# mcu1.net
KiCad netlist of a schematic drawn in Altium Designer
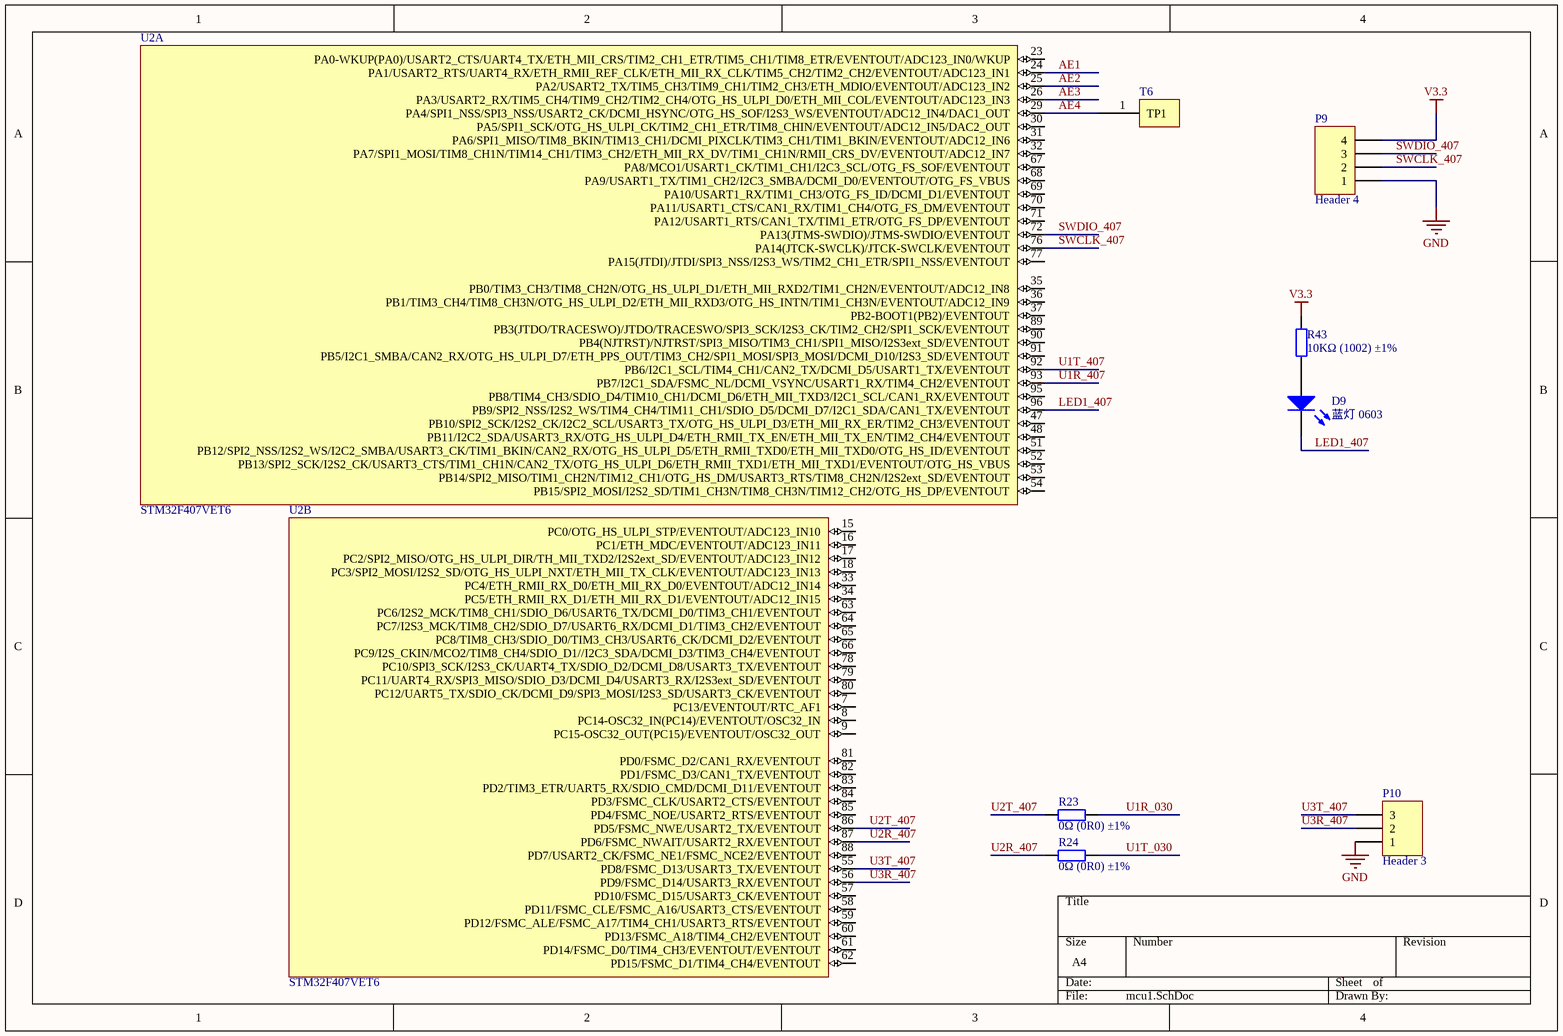
[diagram p0: mcu1.SchDoc]

(export (version "E")
  (design (tool "Eeschema 10.0.6"))
  (components
    (comp (ref "D9")
      (value "蓝灯 0603")
      (footprint "0603_LED_S1")
      (description "发光二极管")
      (libsource (lib "Miscellaneous Devices LC") (part "0603 蓝灯"))
    )
    (comp (ref "P9")
      (value "Header 4")
      (footprint "HDR1X4")
      (description "Header, 4-Pin")
      (fields (field (name "PUBLISHER") "Altium Limited"))
      (libsource (lib "Miscellaneous Connectors") (part "Header 4"))
    )
    (comp (ref "P10")
      (value "Header 3")
      (footprint "HDR1X3")
      (description "Header, 3-Pin")
      (fields (field (name "PUBLISHER") "Altium Limited"))
      (libsource (lib "Miscellaneous Connectors") (part "Header 3"))
    )
    (comp (ref "R23")
      (value "0Ω (0R0) ±1%")
      (footprint "0603_R")
      (description "贴片电阻")
      (libsource (lib "Miscellaneous Devices LC") (part "0603 0Ω (0R0) 1%"))
    )
    (comp (ref "R24")
      (value "0Ω (0R0) ±1%")
      (footprint "0603_R")
      (description "贴片电阻")
      (libsource (lib "Miscellaneous Devices LC") (part "0603 0Ω (0R0) 1%"))
    )
    (comp (ref "R43")
      (value "10KΩ (1002) ±1%")
      (footprint "0603_R")
      (description "贴片电阻")
      (libsource (lib "Miscellaneous Devices LC") (part "0603 10KΩ (1002) 1%"))
    )
    (comp (ref "T6") (value "TP1") (footprint "TP1") (libsource (lib "CHK-I") (part "TP1")))
    (comp (ref "U2")
      (value "STM32F407VET6")
      (footprint "LQFP-100_14x14x05P")
      (description "ARM")
      (libsource (lib "Miscellaneous Devices LC") (part "STM32F407VET6"))
    )
  )
  (nets
    (net (code "1") (name "/AE1") (class "Default")
      (node (ref "U2") (pin "24") (pinfunction "PA1/USART2_RTS/UART4_RX/ETH_RMII_REF_CLK/ETH_MII_RX_CLK/TIM5_CH2/TIM2_CH2/EVENTOUT/ADC123_IN1_24") (pintype "bidirectional"))
    )
    (net (code "2") (name "/AE2") (class "Default")
      (node (ref "U2") (pin "25") (pinfunction "PA2/USART2_TX/TIM5_CH3/TIM9_CH1/TIM2_CH3/ETH_MDIO/EVENTOUT/ADC123_IN2_25") (pintype "bidirectional"))
    )
    (net (code "3") (name "/AE3") (class "Default")
      (node (ref "U2") (pin "26") (pinfunction "PA3/USART2_RX/TIM5_CH4/TIM9_CH2/TIM2_CH4/OTG_HS_ULPI_D0/ETH_MII_COL/EVENTOUT/ADC123_IN3_26") (pintype "bidirectional"))
    )
    (net (code "4") (name "/AE4") (class "Default")
      (node (ref "T6") (pin "1") (pinfunction "TP1_1") (pintype "passive"))
      (node (ref "U2") (pin "29") (pinfunction "PA4/SPI1_NSS/SPI3_NSS/USART2_CK/DCMI_HSYNC/OTG_HS_SOF/I2S3_WS/EVENTOUT/ADC12_IN4/DAC1_OUT_29") (pintype "bidirectional"))
    )
    (net (code "5") (name "/LED1_407") (class "Default")
      (node (ref "D9") (pin "K") (pinfunction "K_K") (pintype "passive"))
      (node (ref "U2") (pin "96") (pinfunction "PB9/SPI2_NSS/I2S2_WS/TIM4_CH4/TIM11_CH1/SDIO_D5/DCMI_D7/I2C1_SDA/CAN1_TX/EVENTOUT_96") (pintype "bidirectional"))
    )
    (net (code "6") (name "/SWCLK_407") (class "Default")
      (node (ref "P9") (pin "2") (pinfunction "2_2") (pintype "passive"))
      (node (ref "U2") (pin "76") (pinfunction "PA14(JTCK-SWCLK)/JTCK-SWCLK/EVENTOUT_76") (pintype "bidirectional"))
    )
    (net (code "7") (name "/SWDIO_407") (class "Default")
      (node (ref "P9") (pin "3") (pinfunction "3_3") (pintype "passive"))
      (node (ref "U2") (pin "72") (pinfunction "PA13(JTMS-SWDIO)/JTMS-SWDIO/EVENTOUT_72") (pintype "bidirectional"))
    )
    (net (code "8") (name "/U1R_030") (class "Default")
      (node (ref "R23") (pin "2") (pinfunction "2_2") (pintype "passive"))
    )
    (net (code "9") (name "/U1R_407") (class "Default")
      (node (ref "U2") (pin "93") (pinfunction "PB7/I2C1_SDA/FSMC_NL/DCMI_VSYNC/USART1_RX/TIM4_CH2/EVENTOUT_93") (pintype "bidirectional"))
    )
    (net (code "10") (name "/U1T_030") (class "Default")
      (node (ref "R24") (pin "2") (pinfunction "2_2") (pintype "passive"))
    )
    (net (code "11") (name "/U1T_407") (class "Default")
      (node (ref "U2") (pin "92") (pinfunction "PB6/I2C1_SCL/TIM4_CH1/CAN2_TX/DCMI_D5/USART1_TX/EVENTOUT_92") (pintype "bidirectional"))
    )
    (net (code "12") (name "/U2R_407") (class "Default")
      (node (ref "R24") (pin "1") (pinfunction "1_1") (pintype "passive"))
      (node (ref "U2") (pin "87") (pinfunction "PD6/FSMC_NWAIT/USART2_RX/EVENTOUT_87") (pintype "bidirectional"))
    )
    (net (code "13") (name "/U2T_407") (class "Default")
      (node (ref "R23") (pin "1") (pinfunction "1_1") (pintype "passive"))
      (node (ref "U2") (pin "86") (pinfunction "PD5/FSMC_NWE/USART2_TX/EVENTOUT_86") (pintype "bidirectional"))
    )
    (net (code "14") (name "/U3R_407") (class "Default")
      (node (ref "P10") (pin "2") (pinfunction "2_2") (pintype "passive"))
      (node (ref "U2") (pin "56") (pinfunction "PD9/FSMC_D14/USART3_RX/EVENTOUT_56") (pintype "bidirectional"))
    )
    (net (code "15") (name "/U3T_407") (class "Default")
      (node (ref "P10") (pin "3") (pinfunction "3_3") (pintype "passive"))
      (node (ref "U2") (pin "55") (pinfunction "PD8/FSMC_D13/USART3_TX/EVENTOUT_55") (pintype "bidirectional"))
    )
    (net (code "16") (name "GND") (class "Default")
      (node (ref "P10") (pin "1") (pinfunction "1_1") (pintype "passive"))
      (node (ref "P9") (pin "1") (pinfunction "1_1") (pintype "passive"))
    )
    (net (code "17") (name "Net-(D9-PadA)") (class "Default")
      (node (ref "D9") (pin "A") (pinfunction "A_A") (pintype "passive"))
      (node (ref "R43") (pin "1") (pinfunction "1_1") (pintype "passive"))
    )
    (net (code "18") (name "V3.3") (class "Default")
      (node (ref "P9") (pin "4") (pinfunction "4_4") (pintype "passive"))
      (node (ref "R43") (pin "2") (pinfunction "2_2") (pintype "passive"))
    )
    (net (code "19") (name "unconnected-(U2A-PA0-WKUP(PA0){slash}USART2_CTS{slash}UART4_TX{slash}ETH_MII_CRS{slash}TIM2_CH1_ETR{slash}TIM5_CH1{slash}TIM8_ETR{slash}EVENTOUT{slash}ADC123_IN0{slash}WKUP-Pad23)") (class "Default")
      (node (ref "U2") (pin "23") (pinfunction "PA0-WKUP(PA0)/USART2_CTS/UART4_TX/ETH_MII_CRS/TIM2_CH1_ETR/TIM5_CH1/TIM8_ETR/EVENTOUT/ADC123_IN0/WKUP_23") (pintype "bidirectional"))
    )
    (net (code "20") (name "unconnected-(U2A-PA5{slash}SPI1_SCK{slash}OTG_HS_ULPI_CK{slash}TIM2_CH1_ETR{slash}TIM8_CHIN{slash}EVENTOUT{slash}ADC12_IN5{slash}DAC2_OUT-Pad30)") (class "Default")
      (node (ref "U2") (pin "30") (pinfunction "PA5/SPI1_SCK/OTG_HS_ULPI_CK/TIM2_CH1_ETR/TIM8_CHIN/EVENTOUT/ADC12_IN5/DAC2_OUT_30") (pintype "bidirectional"))
    )
    (net (code "21") (name "unconnected-(U2A-PA6{slash}SPI1_MISO{slash}TIM8_BKIN{slash}TIM13_CH1{slash}DCMI_PIXCLK{slash}TIM3_CH1{slash}TIM1_BKIN{slash}EVENTOUT{slash}ADC12_IN6-Pad31)") (class "Default")
      (node (ref "U2") (pin "31") (pinfunction "PA6/SPI1_MISO/TIM8_BKIN/TIM13_CH1/DCMI_PIXCLK/TIM3_CH1/TIM1_BKIN/EVENTOUT/ADC12_IN6_31") (pintype "bidirectional"))
    )
    (net (code "22") (name "unconnected-(U2A-PA7{slash}SPI1_MOSI{slash}TIM8_CH1N{slash}TIM14_CH1{slash}TIM3_CH2{slash}ETH_MII_RX_DV{slash}TIM1_CH1N{slash}RMII_CRS_DV{slash}EVENTOUT{slash}ADC12_IN7-Pad32)") (class "Default")
      (node (ref "U2") (pin "32") (pinfunction "PA7/SPI1_MOSI/TIM8_CH1N/TIM14_CH1/TIM3_CH2/ETH_MII_RX_DV/TIM1_CH1N/RMII_CRS_DV/EVENTOUT/ADC12_IN7_32") (pintype "bidirectional"))
    )
    (net (code "23") (name "unconnected-(U2A-PA8{slash}MCO1{slash}USART1_CK{slash}TIM1_CH1{slash}I2C3_SCL{slash}OTG_FS_SOF{slash}EVENTOUT-Pad67)") (class "Default")
      (node (ref "U2") (pin "67") (pinfunction "PA8/MCO1/USART1_CK/TIM1_CH1/I2C3_SCL/OTG_FS_SOF/EVENTOUT_67") (pintype "bidirectional"))
    )
    (net (code "24") (name "unconnected-(U2A-PA9{slash}USART1_TX{slash}TIM1_CH2{slash}I2C3_SMBA{slash}DCMI_D0{slash}EVENTOUT{slash}OTG_FS_VBUS-Pad68)") (class "Default")
      (node (ref "U2") (pin "68") (pinfunction "PA9/USART1_TX/TIM1_CH2/I2C3_SMBA/DCMI_D0/EVENTOUT/OTG_FS_VBUS_68") (pintype "bidirectional"))
    )
    (net (code "25") (name "unconnected-(U2A-PA10{slash}USART1_RX{slash}TIM1_CH3{slash}OTG_FS_ID{slash}DCMI_D1{slash}EVENTOUT-Pad69)") (class "Default")
      (node (ref "U2") (pin "69") (pinfunction "PA10/USART1_RX/TIM1_CH3/OTG_FS_ID/DCMI_D1/EVENTOUT_69") (pintype "bidirectional"))
    )
    (net (code "26") (name "unconnected-(U2A-PA11{slash}USART1_CTS{slash}CAN1_RX{slash}TIM1_CH4{slash}OTG_FS_DM{slash}EVENTOUT-Pad70)") (class "Default")
      (node (ref "U2") (pin "70") (pinfunction "PA11/USART1_CTS/CAN1_RX/TIM1_CH4/OTG_FS_DM/EVENTOUT_70") (pintype "bidirectional"))
    )
    (net (code "27") (name "unconnected-(U2A-PA12{slash}USART1_RTS{slash}CAN1_TX{slash}TIM1_ETR{slash}OTG_FS_DP{slash}EVENTOUT-Pad71)") (class "Default")
      (node (ref "U2") (pin "71") (pinfunction "PA12/USART1_RTS/CAN1_TX/TIM1_ETR/OTG_FS_DP/EVENTOUT_71") (pintype "bidirectional"))
    )
    (net (code "28") (name "unconnected-(U2A-PA15(JTDI){slash}JTDI{slash}SPI3_NSS{slash}I2S3_WS{slash}TIM2_CH1_ETR{slash}SPI1_NSS{slash}EVENTOUT-Pad77)") (class "Default")
      (node (ref "U2") (pin "77") (pinfunction "PA15(JTDI)/JTDI/SPI3_NSS/I2S3_WS/TIM2_CH1_ETR/SPI1_NSS/EVENTOUT_77") (pintype "bidirectional"))
    )
    (net (code "29") (name "unconnected-(U2A-PB0{slash}TIM3_CH3{slash}TIM8_CH2N{slash}OTG_HS_ULPI_D1{slash}ETH_MII_RXD2{slash}TIM1_CH2N{slash}EVENTOUT{slash}ADC12_IN8-Pad35)") (class "Default")
      (node (ref "U2") (pin "35") (pinfunction "PB0/TIM3_CH3/TIM8_CH2N/OTG_HS_ULPI_D1/ETH_MII_RXD2/TIM1_CH2N/EVENTOUT/ADC12_IN8_35") (pintype "bidirectional"))
    )
    (net (code "30") (name "unconnected-(U2A-PB1{slash}TIM3_CH4{slash}TIM8_CH3N{slash}OTG_HS_ULPI_D2{slash}ETH_MII_RXD3{slash}OTG_HS_INTN{slash}TIM1_CH3N{slash}EVENTOUT{slash}ADC12_IN9-Pad36)") (class "Default")
      (node (ref "U2") (pin "36") (pinfunction "PB1/TIM3_CH4/TIM8_CH3N/OTG_HS_ULPI_D2/ETH_MII_RXD3/OTG_HS_INTN/TIM1_CH3N/EVENTOUT/ADC12_IN9_36") (pintype "bidirectional"))
    )
    (net (code "31") (name "unconnected-(U2A-PB2-BOOT1(PB2){slash}EVENTOUT-Pad37)") (class "Default")
      (node (ref "U2") (pin "37") (pinfunction "PB2-BOOT1(PB2)/EVENTOUT_37") (pintype "bidirectional"))
    )
    (net (code "32") (name "unconnected-(U2A-PB3(JTDO{slash}TRACESWO){slash}JTDO{slash}TRACESWO{slash}SPI3_SCK{slash}I2S3_CK{slash}TIM2_CH2{slash}SPI1_SCK{slash}EVENTOUT-Pad89)") (class "Default")
      (node (ref "U2") (pin "89") (pinfunction "PB3(JTDO/TRACESWO)/JTDO/TRACESWO/SPI3_SCK/I2S3_CK/TIM2_CH2/SPI1_SCK/EVENTOUT_89") (pintype "bidirectional"))
    )
    (net (code "33") (name "unconnected-(U2A-PB4(NJTRST){slash}NJTRST{slash}SPI3_MISO{slash}TIM3_CH1{slash}SPI1_MISO{slash}I2S3ext_SD{slash}EVENTOUT-Pad90)") (class "Default")
      (node (ref "U2") (pin "90") (pinfunction "PB4(NJTRST)/NJTRST/SPI3_MISO/TIM3_CH1/SPI1_MISO/I2S3ext_SD/EVENTOUT_90") (pintype "bidirectional"))
    )
    (net (code "34") (name "unconnected-(U2A-PB5{slash}I2C1_SMBA{slash}CAN2_RX{slash}OTG_HS_ULPI_D7{slash}ETH_PPS_OUT{slash}TIM3_CH2{slash}SPI1_MOSI{slash}SPI3_MOSI{slash}DCMI_D10{slash}I2S3_SD{slash}EVENTOUT-Pad91)") (class "Default")
      (node (ref "U2") (pin "91") (pinfunction "PB5/I2C1_SMBA/CAN2_RX/OTG_HS_ULPI_D7/ETH_PPS_OUT/TIM3_CH2/SPI1_MOSI/SPI3_MOSI/DCMI_D10/I2S3_SD/EVENTOUT_91") (pintype "bidirectional"))
    )
    (net (code "35") (name "unconnected-(U2A-PB8{slash}TIM4_CH3{slash}SDIO_D4{slash}TIM10_CH1{slash}DCMI_D6{slash}ETH_MII_TXD3{slash}I2C1_SCL{slash}CAN1_RX{slash}EVENTOUT-Pad95)") (class "Default")
      (node (ref "U2") (pin "95") (pinfunction "PB8/TIM4_CH3/SDIO_D4/TIM10_CH1/DCMI_D6/ETH_MII_TXD3/I2C1_SCL/CAN1_RX/EVENTOUT_95") (pintype "bidirectional"))
    )
    (net (code "36") (name "unconnected-(U2A-PB10{slash}SPI2_SCK{slash}I2S2_CK{slash}I2C2_SCL{slash}USART3_TX{slash}OTG_HS_ULPI_D3{slash}ETH_MII_RX_ER{slash}TIM2_CH3{slash}EVENTOUT-Pad47)") (class "Default")
      (node (ref "U2") (pin "47") (pinfunction "PB10/SPI2_SCK/I2S2_CK/I2C2_SCL/USART3_TX/OTG_HS_ULPI_D3/ETH_MII_RX_ER/TIM2_CH3/EVENTOUT_47") (pintype "bidirectional"))
    )
    (net (code "37") (name "unconnected-(U2A-PB11{slash}I2C2_SDA{slash}USART3_RX{slash}OTG_HS_ULPI_D4{slash}ETH_RMII_TX_EN{slash}ETH_MII_TX_EN{slash}TIM2_CH4{slash}EVENTOUT-Pad48)") (class "Default")
      (node (ref "U2") (pin "48") (pinfunction "PB11/I2C2_SDA/USART3_RX/OTG_HS_ULPI_D4/ETH_RMII_TX_EN/ETH_MII_TX_EN/TIM2_CH4/EVENTOUT_48") (pintype "bidirectional"))
    )
    (net (code "38") (name "unconnected-(U2A-PB12{slash}SPI2_NSS{slash}I2S2_WS{slash}I2C2_SMBA{slash}USART3_CK{slash}TIM1_BKIN{slash}CAN2_RX{slash}OTG_HS_ULPI_D5{slash}ETH_RMII_TXD0{slash}ETH_MII_TXD0{slash}OTG_HS_ID{slash}EVENTOUT-Pad51)") (class "Default")
      (node (ref "U2") (pin "51") (pinfunction "PB12/SPI2_NSS/I2S2_WS/I2C2_SMBA/USART3_CK/TIM1_BKIN/CAN2_RX/OTG_HS_ULPI_D5/ETH_RMII_TXD0/ETH_MII_TXD0/OTG_HS_ID/EVENTOUT_51") (pintype "bidirectional"))
    )
    (net (code "39") (name "unconnected-(U2A-PB13{slash}SPI2_SCK{slash}I2S2_CK{slash}USART3_CTS{slash}TIM1_CH1N{slash}CAN2_TX{slash}OTG_HS_ULPI_D6{slash}ETH_RMII_TXD1{slash}ETH_MII_TXD1{slash}EVENTOUT{slash}OTG_HS_VBUS-Pad52)") (class "Default")
      (node (ref "U2") (pin "52") (pinfunction "PB13/SPI2_SCK/I2S2_CK/USART3_CTS/TIM1_CH1N/CAN2_TX/OTG_HS_ULPI_D6/ETH_RMII_TXD1/ETH_MII_TXD1/EVENTOUT/OTG_HS_VBUS_52") (pintype "bidirectional"))
    )
    (net (code "40") (name "unconnected-(U2A-PB14{slash}SPI2_MISO{slash}TIM1_CH2N{slash}TIM12_CH1{slash}OTG_HS_DM{slash}USART3_RTS{slash}TIM8_CH2N{slash}I2S2ext_SD{slash}EVENTOUT-Pad53)") (class "Default")
      (node (ref "U2") (pin "53") (pinfunction "PB14/SPI2_MISO/TIM1_CH2N/TIM12_CH1/OTG_HS_DM/USART3_RTS/TIM8_CH2N/I2S2ext_SD/EVENTOUT_53") (pintype "bidirectional"))
    )
    (net (code "41") (name "unconnected-(U2A-PB15{slash}SPI2_MOSI{slash}I2S2_SD{slash}TIM1_CH3N{slash}TIM8_CH3N{slash}TIM12_CH2{slash}OTG_HS_DP{slash}EVENTOUT-Pad54)") (class "Default")
      (node (ref "U2") (pin "54") (pinfunction "PB15/SPI2_MOSI/I2S2_SD/TIM1_CH3N/TIM8_CH3N/TIM12_CH2/OTG_HS_DP/EVENTOUT_54") (pintype "bidirectional"))
    )
    (net (code "42") (name "unconnected-(U2B-PC0{slash}OTG_HS_ULPI_STP{slash}EVENTOUT{slash}ADC123_IN10-Pad15)") (class "Default")
      (node (ref "U2") (pin "15") (pinfunction "PC0/OTG_HS_ULPI_STP/EVENTOUT/ADC123_IN10_15") (pintype "bidirectional"))
    )
    (net (code "43") (name "unconnected-(U2B-PC1{slash}ETH_MDC{slash}EVENTOUT{slash}ADC123_IN11-Pad16)") (class "Default")
      (node (ref "U2") (pin "16") (pinfunction "PC1/ETH_MDC/EVENTOUT/ADC123_IN11_16") (pintype "bidirectional"))
    )
    (net (code "44") (name "unconnected-(U2B-PC2{slash}SPI2_MISO{slash}OTG_HS_ULPI_DIR{slash}TH_MII_TXD2{slash}I2S2ext_SD{slash}EVENTOUT{slash}ADC123_IN12-Pad17)") (class "Default")
      (node (ref "U2") (pin "17") (pinfunction "PC2/SPI2_MISO/OTG_HS_ULPI_DIR/TH_MII_TXD2/I2S2ext_SD/EVENTOUT/ADC123_IN12_17") (pintype "bidirectional"))
    )
    (net (code "45") (name "unconnected-(U2B-PC3{slash}SPI2_MOSI{slash}I2S2_SD{slash}OTG_HS_ULPI_NXT{slash}ETH_MII_TX_CLK{slash}EVENTOUT{slash}ADC123_IN13-Pad18)") (class "Default")
      (node (ref "U2") (pin "18") (pinfunction "PC3/SPI2_MOSI/I2S2_SD/OTG_HS_ULPI_NXT/ETH_MII_TX_CLK/EVENTOUT/ADC123_IN13_18") (pintype "bidirectional"))
    )
    (net (code "46") (name "unconnected-(U2B-PC4{slash}ETH_RMII_RX_D0{slash}ETH_MII_RX_D0{slash}EVENTOUT{slash}ADC12_IN14-Pad33)") (class "Default")
      (node (ref "U2") (pin "33") (pinfunction "PC4/ETH_RMII_RX_D0/ETH_MII_RX_D0/EVENTOUT/ADC12_IN14_33") (pintype "bidirectional"))
    )
    (net (code "47") (name "unconnected-(U2B-PC5{slash}ETH_RMII_RX_D1{slash}ETH_MII_RX_D1{slash}EVENTOUT{slash}ADC12_IN15-Pad34)") (class "Default")
      (node (ref "U2") (pin "34") (pinfunction "PC5/ETH_RMII_RX_D1/ETH_MII_RX_D1/EVENTOUT/ADC12_IN15_34") (pintype "bidirectional"))
    )
    (net (code "48") (name "unconnected-(U2B-PC6{slash}I2S2_MCK{slash}TIM8_CH1{slash}SDIO_D6{slash}USART6_TX{slash}DCMI_D0{slash}TIM3_CH1{slash}EVENTOUT-Pad63)") (class "Default")
      (node (ref "U2") (pin "63") (pinfunction "PC6/I2S2_MCK/TIM8_CH1/SDIO_D6/USART6_TX/DCMI_D0/TIM3_CH1/EVENTOUT_63") (pintype "bidirectional"))
    )
    (net (code "49") (name "unconnected-(U2B-PC7{slash}I2S3_MCK{slash}TIM8_CH2{slash}SDIO_D7{slash}USART6_RX{slash}DCMI_D1{slash}TIM3_CH2{slash}EVENTOUT-Pad64)") (class "Default")
      (node (ref "U2") (pin "64") (pinfunction "PC7/I2S3_MCK/TIM8_CH2/SDIO_D7/USART6_RX/DCMI_D1/TIM3_CH2/EVENTOUT_64") (pintype "bidirectional"))
    )
    (net (code "50") (name "unconnected-(U2B-PC8{slash}TIM8_CH3{slash}SDIO_D0{slash}TIM3_CH3{slash}USART6_CK{slash}DCMI_D2{slash}EVENTOUT-Pad65)") (class "Default")
      (node (ref "U2") (pin "65") (pinfunction "PC8/TIM8_CH3/SDIO_D0/TIM3_CH3/USART6_CK/DCMI_D2/EVENTOUT_65") (pintype "bidirectional"))
    )
    (net (code "51") (name "unconnected-(U2B-PC9{slash}I2S_CKIN{slash}MCO2{slash}TIM8_CH4{slash}SDIO_D1{slash}{slash}I2C3_SDA{slash}DCMI_D3{slash}TIM3_CH4{slash}EVENTOUT-Pad66)") (class "Default")
      (node (ref "U2") (pin "66") (pinfunction "PC9/I2S_CKIN/MCO2/TIM8_CH4/SDIO_D1//I2C3_SDA/DCMI_D3/TIM3_CH4/EVENTOUT_66") (pintype "bidirectional"))
    )
    (net (code "52") (name "unconnected-(U2B-PC10{slash}SPI3_SCK{slash}I2S3_CK{slash}UART4_TX{slash}SDIO_D2{slash}DCMI_D8{slash}USART3_TX{slash}EVENTOUT-Pad78)") (class "Default")
      (node (ref "U2") (pin "78") (pinfunction "PC10/SPI3_SCK/I2S3_CK/UART4_TX/SDIO_D2/DCMI_D8/USART3_TX/EVENTOUT_78") (pintype "bidirectional"))
    )
    (net (code "53") (name "unconnected-(U2B-PC11{slash}UART4_RX{slash}SPI3_MISO{slash}SDIO_D3{slash}DCMI_D4{slash}USART3_RX{slash}I2S3ext_SD{slash}EVENTOUT-Pad79)") (class "Default")
      (node (ref "U2") (pin "79") (pinfunction "PC11/UART4_RX/SPI3_MISO/SDIO_D3/DCMI_D4/USART3_RX/I2S3ext_SD/EVENTOUT_79") (pintype "bidirectional"))
    )
    (net (code "54") (name "unconnected-(U2B-PC12{slash}UART5_TX{slash}SDIO_CK{slash}DCMI_D9{slash}SPI3_MOSI{slash}I2S3_SD{slash}USART3_CK{slash}EVENTOUT-Pad80)") (class "Default")
      (node (ref "U2") (pin "80") (pinfunction "PC12/UART5_TX/SDIO_CK/DCMI_D9/SPI3_MOSI/I2S3_SD/USART3_CK/EVENTOUT_80") (pintype "bidirectional"))
    )
    (net (code "55") (name "unconnected-(U2B-PC13{slash}EVENTOUT{slash}RTC_AF1-Pad7)") (class "Default")
      (node (ref "U2") (pin "7") (pinfunction "PC13/EVENTOUT/RTC_AF1_7") (pintype "bidirectional"))
    )
    (net (code "56") (name "unconnected-(U2B-PC14-OSC32_IN(PC14){slash}EVENTOUT{slash}OSC32_IN-Pad8)") (class "Default")
      (node (ref "U2") (pin "8") (pinfunction "PC14-OSC32_IN(PC14)/EVENTOUT/OSC32_IN_8") (pintype "bidirectional"))
    )
    (net (code "57") (name "unconnected-(U2B-PC15-OSC32_OUT(PC15){slash}EVENTOUT{slash}OSC32_OUT-Pad9)") (class "Default")
      (node (ref "U2") (pin "9") (pinfunction "PC15-OSC32_OUT(PC15)/EVENTOUT/OSC32_OUT_9") (pintype "bidirectional"))
    )
    (net (code "58") (name "unconnected-(U2B-PD0{slash}FSMC_D2{slash}CAN1_RX{slash}EVENTOUT-Pad81)") (class "Default")
      (node (ref "U2") (pin "81") (pinfunction "PD0/FSMC_D2/CAN1_RX/EVENTOUT_81") (pintype "bidirectional"))
    )
    (net (code "59") (name "unconnected-(U2B-PD1{slash}FSMC_D3{slash}CAN1_TX{slash}EVENTOUT-Pad82)") (class "Default")
      (node (ref "U2") (pin "82") (pinfunction "PD1/FSMC_D3/CAN1_TX/EVENTOUT_82") (pintype "bidirectional"))
    )
    (net (code "60") (name "unconnected-(U2B-PD2{slash}TIM3_ETR{slash}UART5_RX{slash}SDIO_CMD{slash}DCMI_D11{slash}EVENTOUT-Pad83)") (class "Default")
      (node (ref "U2") (pin "83") (pinfunction "PD2/TIM3_ETR/UART5_RX/SDIO_CMD/DCMI_D11/EVENTOUT_83") (pintype "bidirectional"))
    )
    (net (code "61") (name "unconnected-(U2B-PD3{slash}FSMC_CLK{slash}USART2_CTS{slash}EVENTOUT-Pad84)") (class "Default")
      (node (ref "U2") (pin "84") (pinfunction "PD3/FSMC_CLK/USART2_CTS/EVENTOUT_84") (pintype "bidirectional"))
    )
    (net (code "62") (name "unconnected-(U2B-PD4{slash}FSMC_NOE{slash}USART2_RTS{slash}EVENTOUT-Pad85)") (class "Default")
      (node (ref "U2") (pin "85") (pinfunction "PD4/FSMC_NOE/USART2_RTS/EVENTOUT_85") (pintype "bidirectional"))
    )
    (net (code "63") (name "unconnected-(U2B-PD7{slash}USART2_CK{slash}FSMC_NE1{slash}FSMC_NCE2{slash}EVENTOUT-Pad88)") (class "Default")
      (node (ref "U2") (pin "88") (pinfunction "PD7/USART2_CK/FSMC_NE1/FSMC_NCE2/EVENTOUT_88") (pintype "bidirectional"))
    )
    (net (code "64") (name "unconnected-(U2B-PD10{slash}FSMC_D15{slash}USART3_CK{slash}EVENTOUT-Pad57)") (class "Default")
      (node (ref "U2") (pin "57") (pinfunction "PD10/FSMC_D15/USART3_CK/EVENTOUT_57") (pintype "bidirectional"))
    )
    (net (code "65") (name "unconnected-(U2B-PD11{slash}FSMC_CLE{slash}FSMC_A16{slash}USART3_CTS{slash}EVENTOUT-Pad58)") (class "Default")
      (node (ref "U2") (pin "58") (pinfunction "PD11/FSMC_CLE/FSMC_A16/USART3_CTS/EVENTOUT_58") (pintype "bidirectional"))
    )
    (net (code "66") (name "unconnected-(U2B-PD12{slash}FSMC_ALE{slash}FSMC_A17{slash}TIM4_CH1{slash}USART3_RTS{slash}EVENTOUT-Pad59)") (class "Default")
      (node (ref "U2") (pin "59") (pinfunction "PD12/FSMC_ALE/FSMC_A17/TIM4_CH1/USART3_RTS/EVENTOUT_59") (pintype "bidirectional"))
    )
    (net (code "67") (name "unconnected-(U2B-PD13{slash}FSMC_A18{slash}TIM4_CH2{slash}EVENTOUT-Pad60)") (class "Default")
      (node (ref "U2") (pin "60") (pinfunction "PD13/FSMC_A18/TIM4_CH2/EVENTOUT_60") (pintype "bidirectional"))
    )
    (net (code "68") (name "unconnected-(U2B-PD14{slash}FSMC_D0{slash}TIM4_CH3{slash}EVENTOUT{slash}EVENTOUT-Pad61)") (class "Default")
      (node (ref "U2") (pin "61") (pinfunction "PD14/FSMC_D0/TIM4_CH3/EVENTOUT/EVENTOUT_61") (pintype "bidirectional"))
    )
    (net (code "69") (name "unconnected-(U2B-PD15{slash}FSMC_D1{slash}TIM4_CH4{slash}EVENTOUT-Pad62)") (class "Default")
      (node (ref "U2") (pin "62") (pinfunction "PD15/FSMC_D1/TIM4_CH4/EVENTOUT_62") (pintype "bidirectional"))
    )
  )
)
